# Mach3.net
KiCad netlist of a schematic drawn in Altium Designer
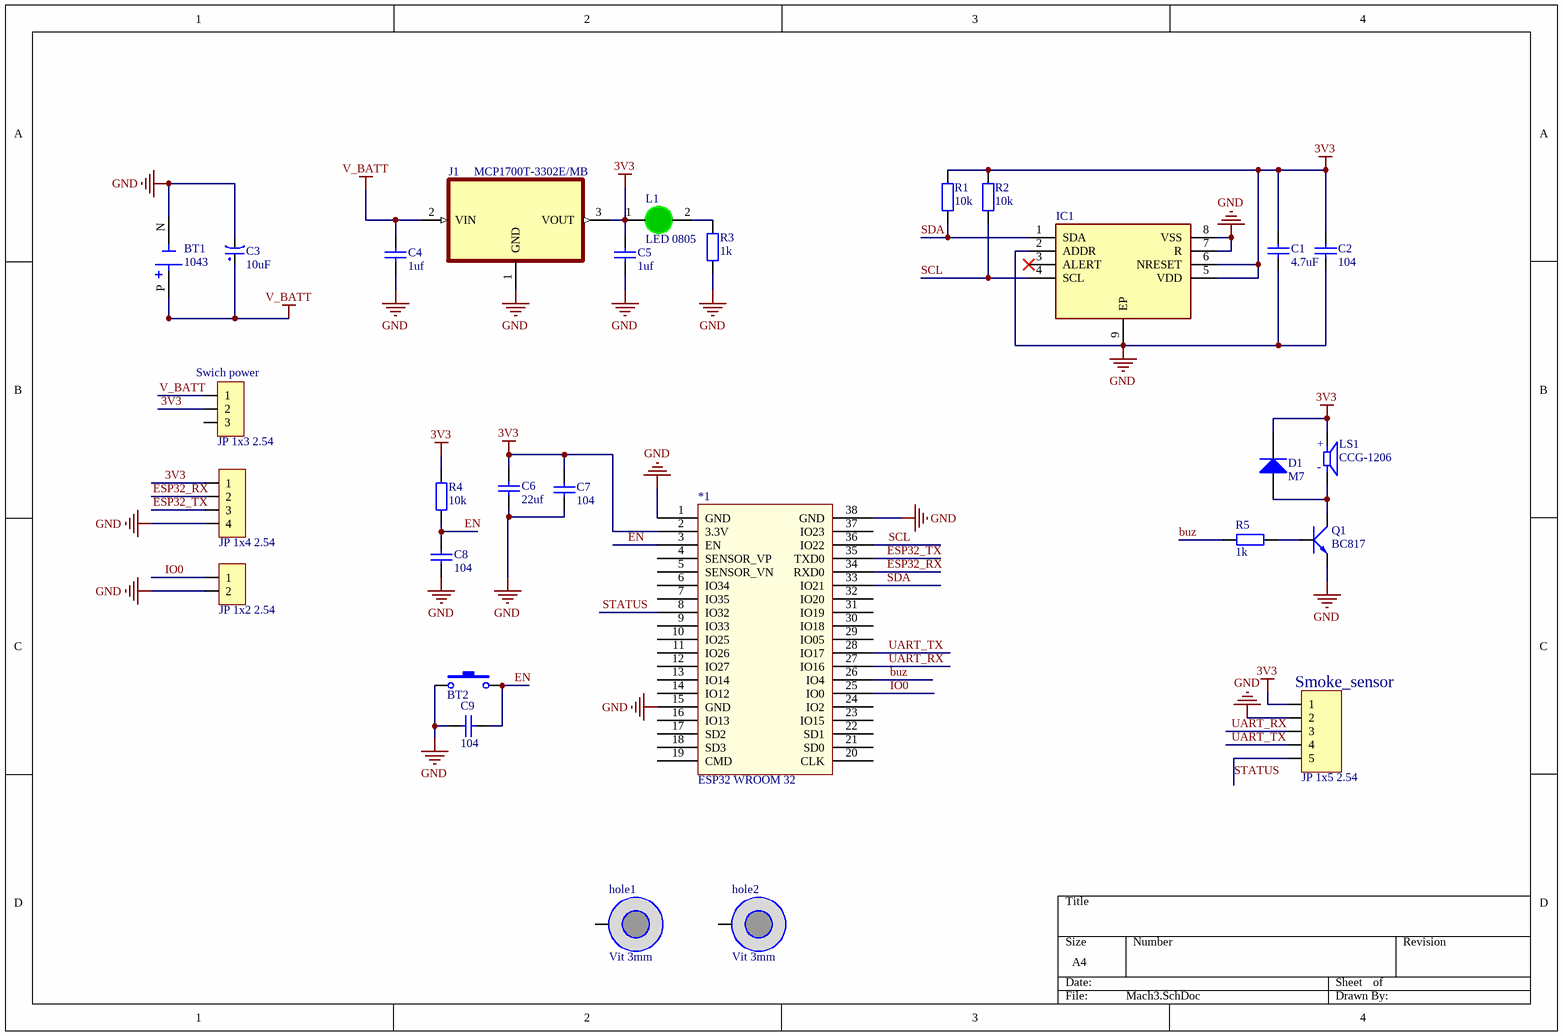
[diagram p0: Mach3.SchDoc]

(export (version "E")
  (design (tool "Eeschema 10.0.6"))
  (components
    (comp (ref "*1")
      (value "ESP32 WROOM 32")
      (footprint "ESP32-WROOM-32D")
      (libsource (lib "Altium_Lib_by_KhueNguyenCreator") (part "ESP32 WROOM 32"))
    )
    (comp (ref "BT1")
      (value "1043")
      (footprint "BAT_1043")
      (description "THM Holder for 18650 Battery")
      (fields (field (name "MF") "Keystone Electronics"))
      (libsource (lib "Mach3") (part "1043"))
    )
    (comp (ref "BT2")
      (value "Nut Nhan 2 Chan SMD 3x6x2.5")
      (footprint "Nut Nhan 2 Chan SMD 3x6x2.5")
      (libsource (lib "Altium_Lib_by_KhueNguyenCreator") (part "Nut Nhan 2 Chan SMD 3x6x2.5"))
    )
    (comp (ref "C1")
      (value "4.7uF")
      (footprint "tu 0805")
      (description "Dán")
      (libsource (lib "Altium_Lib_by_KhueNguyenCreator") (part "Tu 0805 104 50V 10%"))
    )
    (comp (ref "C2")
      (value "104")
      (footprint "tu 0805")
      (description "Dán")
      (libsource (lib "Altium_Lib_by_KhueNguyenCreator") (part "Tu 0805 104 50V 10%"))
    )
    (comp (ref "C3")
      (value "10uF")
      (footprint "tu hoa 8mm")
      (description "Cắm")
      (libsource (lib "Altium_Lib_by_KhueNguyenCreator") (part "Tu Hoa 0.1uF 50V 5x11"))
    )
    (comp (ref "C4")
      (value "1uf")
      (footprint "tu 0805")
      (description "Dán")
      (libsource (lib "Altium_Lib_by_KhueNguyenCreator") (part "Tu 0805 104 50V 10%"))
    )
    (comp (ref "C5")
      (value "1uf")
      (footprint "tu 0805")
      (description "Dán")
      (libsource (lib "Altium_Lib_by_KhueNguyenCreator") (part "Tu 0805 104 50V 10%"))
    )
    (comp (ref "C6")
      (value "22uf")
      (footprint "tu 0805")
      (description "Dán")
      (libsource (lib "Altium_Lib_by_KhueNguyenCreator") (part "Tu 0805 104 50V 10%"))
    )
    (comp (ref "C7")
      (value "104")
      (footprint "tu 0805")
      (description "Dán")
      (libsource (lib "Altium_Lib_by_KhueNguyenCreator") (part "Tu 0805 104 50V 10%"))
    )
    (comp (ref "C8")
      (value "104")
      (footprint "tu 0805")
      (description "Dán")
      (libsource (lib "Altium_Lib_by_KhueNguyenCreator") (part "Tu 0805 104 50V 10%"))
    )
    (comp (ref "C9")
      (value "104")
      (footprint "tu 0805")
      (description "Dán")
      (libsource (lib "Altium_Lib_by_KhueNguyenCreator") (part "Tu 0805 104 50V 10%"))
    )
    (comp (ref "D1")
      (value "M7")
      (footprint "DIODE SMA")
      (description "Dán")
      (libsource (lib "Altium_Lib_by_KhueNguyenCreator") (part "Diode M7 ( 4007 )"))
    )
    (comp (ref "hole1") (value "Vit 3mm") (footprint "Screw 3.0") (libsource (lib "LPSON") (part "Vit 3mm")))
    (comp (ref "hole2") (value "Vit 3mm") (footprint "Screw 3.0") (libsource (lib "LPSON") (part "Vit 3mm")))
    (comp (ref "IC1")
      (value "~")
      (footprint "SON50P250X250X100-9N-D")
      (description "Integrated Circuit")
      (fields
        (field (name "MANUFACTURER_PART_NUMBER") "SHT30-DIS-B10KS")
        (field (name "MOUSER PART NUMBER") "403-SHT30-DIS-B10KS")
      )
      (libsource (lib "Mach3") (part "SHT30-DIS-B10KS_1"))
    )
    (comp (ref "J1")
      (value "MCP1700T-3302E/MB")
      (footprint "MCP1700T-3302E/MB")
      (description "Linear Voltage Regulator IC Positive Fixed 1 Output 250mA SOT-89-3")
      (fields (field (name "MF") "Microchip"))
      (libsource (lib "Mach3") (part "MCP1700T-3302E/MB"))
    )
    (comp (ref "JP1")
      (value "JP 1x5 2.54")
      (footprint "JP 1x5 CT")
      (description "Cắm")
      (libsource (lib "Altium_Lib_by_KhueNguyenCreator") (part "JP 1x5 2.54 Cai Thang"))
    )
    (comp (ref "JP2")
      (value "JP 1x4 2.54")
      (footprint "JP 1x4 CT")
      (description "Cắm")
      (libsource (lib "Altium_Lib_by_KhueNguyenCreator") (part "JP 1x4 2.54 Cai Thang"))
    )
    (comp (ref "JP3")
      (value "JP 1x2 2.54")
      (footprint "JP 1x2 DT")
      (description "Cắm")
      (libsource (lib "Altium_Lib_by_KhueNguyenCreator") (part "JP 1x2 2.54 Duc Thang"))
    )
    (comp (ref "JP4")
      (value "JP 1x3 2.54")
      (footprint "JP 1x3 DT")
      (description "Cắm")
      (libsource (lib "Altium_Lib_by_KhueNguyenCreator") (part "JP 1x3 2.54 Duc Thang"))
    )
    (comp (ref "L1")
      (value "LED 0805")
      (footprint "LED-1206-Green")
      (description "Dán")
      (libsource (lib "Altium_Lib_by_KhueNguyenCreator") (part "LED 1206 Xanh La"))
    )
    (comp (ref "LS1")
      (value "CCG-1206")
      (footprint "CUI_CCG-1206")
      (description "12 mm, 5 V, 85 dB, Through Hole, Sealed, Magnetic Audio Transducer Buzzer")
      (fields (field (name "MF") "Same Sky"))
      (libsource (lib "Mach3") (part "CCG-1206"))
    )
    (comp (ref "Q1")
      (value "BC817")
      (footprint "SOT-23")
      (description "SOT-23 - C8658")
      (libsource (lib "Altium_Lib_by_KhueNguyenCreator") (part "Trans BC817"))
    )
    (comp (ref "R1")
      (value "10k")
      (footprint "tro smd 0805")
      (description "Dán")
      (libsource (lib "Altium_Lib_by_KhueNguyenCreator") (part "Tro 0805 1% 1k"))
    )
    (comp (ref "R2")
      (value "10k")
      (footprint "tro smd 0805")
      (description "Dán")
      (libsource (lib "Altium_Lib_by_KhueNguyenCreator") (part "Tro 0805 1% 1k"))
    )
    (comp (ref "R3")
      (value "1k")
      (footprint "tro smd 0805")
      (description "Dán")
      (libsource (lib "Altium_Lib_by_KhueNguyenCreator") (part "Tro 0805 1% 1k"))
    )
    (comp (ref "R4")
      (value "10k")
      (footprint "tro smd 0805")
      (description "Dán")
      (libsource (lib "Altium_Lib_by_KhueNguyenCreator") (part "Tro 0805 1% 1k"))
    )
    (comp (ref "R5")
      (value "1k")
      (footprint "tro smd 0805")
      (description "Dán")
      (libsource (lib "Altium_Lib_by_KhueNguyenCreator") (part "Tro 0805 1% 1k"))
    )
  )
  (nets
    (net (code "1") (name "/EN") (class "Default")
      (node (ref "*1") (pin "3") (pinfunction "EN_3") (pintype "passive"))
      (node (ref "BT2") (pin "2") (pinfunction "2_2") (pintype "passive"))
      (node (ref "C8") (pin "1") (pinfunction "1_1") (pintype "passive"))
      (node (ref "C9") (pin "2") (pinfunction "2_2") (pintype "passive"))
      (node (ref "R4") (pin "1") (pinfunction "1_1") (pintype "passive"))
    )
    (net (code "2") (name "/ESP32_RX") (class "Default")
      (node (ref "*1") (pin "34") (pinfunction "RXD0_34") (pintype "passive"))
      (node (ref "JP2") (pin "2") (pinfunction "2_2") (pintype "passive"))
    )
    (net (code "3") (name "/ESP32_TX") (class "Default")
      (node (ref "*1") (pin "35") (pinfunction "TXD0_35") (pintype "passive"))
      (node (ref "JP2") (pin "3") (pinfunction "3_3") (pintype "passive"))
    )
    (net (code "4") (name "/IO0") (class "Default")
      (node (ref "*1") (pin "25") (pinfunction "IO0_25") (pintype "passive"))
      (node (ref "JP3") (pin "1") (pinfunction "1_1") (pintype "passive"))
    )
    (net (code "5") (name "/SCL") (class "Default")
      (node (ref "*1") (pin "36") (pinfunction "IO22_36") (pintype "passive"))
      (node (ref "IC1") (pin "4") (pinfunction "SCL_4") (pintype "passive"))
      (node (ref "R2") (pin "1") (pinfunction "1_1") (pintype "passive"))
    )
    (net (code "6") (name "/SDA") (class "Default")
      (node (ref "*1") (pin "33") (pinfunction "IO21_33") (pintype "passive"))
      (node (ref "IC1") (pin "1") (pinfunction "SDA_1") (pintype "passive"))
      (node (ref "R1") (pin "1") (pinfunction "1_1") (pintype "passive"))
    )
    (net (code "7") (name "/STATUS") (class "Default")
      (node (ref "*1") (pin "8") (pinfunction "IO32_8") (pintype "passive"))
      (node (ref "JP1") (pin "5") (pinfunction "5_5") (pintype "passive"))
    )
    (net (code "8") (name "/UART_RX") (class "Default")
      (node (ref "*1") (pin "27") (pinfunction "IO16_27") (pintype "passive"))
      (node (ref "JP1") (pin "3") (pinfunction "3_3") (pintype "passive"))
    )
    (net (code "9") (name "/UART_TX") (class "Default")
      (node (ref "*1") (pin "28") (pinfunction "IO17_28") (pintype "passive"))
      (node (ref "JP1") (pin "4") (pinfunction "4_4") (pintype "passive"))
    )
    (net (code "10") (name "/buz") (class "Default")
      (node (ref "*1") (pin "26") (pinfunction "IO4_26") (pintype "passive"))
      (node (ref "R5") (pin "2") (pinfunction "2_2") (pintype "passive"))
    )
    (net (code "11") (name "3V3") (class "Default")
      (node (ref "*1") (pin "2") (pinfunction "3.3V_2") (pintype "passive"))
      (node (ref "C1") (pin "1") (pinfunction "1_1") (pintype "passive"))
      (node (ref "C2") (pin "1") (pinfunction "1_1") (pintype "passive"))
      (node (ref "C5") (pin "1") (pinfunction "1_1") (pintype "passive"))
      (node (ref "C6") (pin "1") (pinfunction "1_1") (pintype "passive"))
      (node (ref "C7") (pin "1") (pinfunction "1_1") (pintype "passive"))
      (node (ref "D1") (pin "2") (pinfunction "K_2") (pintype "passive"))
      (node (ref "IC1") (pin "5") (pinfunction "VDD_5") (pintype "passive"))
      (node (ref "IC1") (pin "6") (pinfunction "NRESET_6") (pintype "passive"))
      (node (ref "J1") (pin "3") (pinfunction "VOUT_3") (pintype "output"))
      (node (ref "JP1") (pin "1") (pinfunction "1_1") (pintype "passive"))
      (node (ref "JP2") (pin "1") (pinfunction "1_1") (pintype "passive"))
      (node (ref "JP4") (pin "2") (pinfunction "2_2") (pintype "passive"))
      (node (ref "L1") (pin "1") (pinfunction "A_1") (pintype "passive"))
      (node (ref "LS1") (pin "P") (pinfunction "P_P") (pintype "passive"))
      (node (ref "R1") (pin "2") (pinfunction "2_2") (pintype "passive"))
      (node (ref "R2") (pin "2") (pinfunction "2_2") (pintype "passive"))
      (node (ref "R4") (pin "2") (pinfunction "2_2") (pintype "passive"))
    )
    (net (code "12") (name "GND") (class "Default")
      (node (ref "*1") (pin "1") (pinfunction "GND_1") (pintype "passive"))
      (node (ref "*1") (pin "15") (pinfunction "GND_15") (pintype "passive"))
      (node (ref "*1") (pin "38") (pinfunction "GND_38") (pintype "passive"))
      (node (ref "BT1") (pin "N") (pinfunction "NEG_N") (pintype "passive"))
      (node (ref "BT2") (pin "1") (pinfunction "1_1") (pintype "passive"))
      (node (ref "C1") (pin "2") (pinfunction "2_2") (pintype "passive"))
      (node (ref "C2") (pin "2") (pinfunction "2_2") (pintype "passive"))
      (node (ref "C3") (pin "2") (pinfunction "2_2") (pintype "passive"))
      (node (ref "C4") (pin "2") (pinfunction "2_2") (pintype "passive"))
      (node (ref "C5") (pin "2") (pinfunction "2_2") (pintype "passive"))
      (node (ref "C6") (pin "2") (pinfunction "2_2") (pintype "passive"))
      (node (ref "C7") (pin "2") (pinfunction "2_2") (pintype "passive"))
      (node (ref "C8") (pin "2") (pinfunction "2_2") (pintype "passive"))
      (node (ref "C9") (pin "1") (pinfunction "1_1") (pintype "passive"))
      (node (ref "IC1") (pin "2") (pinfunction "ADDR_2") (pintype "passive"))
      (node (ref "IC1") (pin "7") (pinfunction "R_7") (pintype "passive"))
      (node (ref "IC1") (pin "8") (pinfunction "VSS_8") (pintype "passive"))
      (node (ref "IC1") (pin "9") (pinfunction "EP_9") (pintype "passive"))
      (node (ref "J1") (pin "1") (pinfunction "GND_1") (pintype "passive"))
      (node (ref "JP1") (pin "2") (pinfunction "2_2") (pintype "passive"))
      (node (ref "JP2") (pin "4") (pinfunction "4_4") (pintype "passive"))
      (node (ref "JP3") (pin "2") (pinfunction "2_2") (pintype "passive"))
      (node (ref "Q1") (pin "2") (pinfunction "E_2") (pintype "passive"))
      (node (ref "R3") (pin "1") (pinfunction "1_1") (pintype "passive"))
    )
    (net (code "13") (name "Net-(D1-A)") (class "Default")
      (node (ref "D1") (pin "1") (pinfunction "A_1") (pintype "passive"))
      (node (ref "LS1") (pin "M") (pinfunction "M_M") (pintype "passive"))
      (node (ref "Q1") (pin "3") (pinfunction "C_3") (pintype "passive"))
    )
    (net (code "14") (name "Net-(L1-K)") (class "Default")
      (node (ref "L1") (pin "2") (pinfunction "K_2") (pintype "passive"))
      (node (ref "R3") (pin "2") (pinfunction "2_2") (pintype "passive"))
    )
    (net (code "15") (name "Net-(Q1-B)") (class "Default")
      (node (ref "Q1") (pin "1") (pinfunction "B_1") (pintype "passive"))
      (node (ref "R5") (pin "1") (pinfunction "1_1") (pintype "passive"))
    )
    (net (code "16") (name "V_BATT") (class "Default")
      (node (ref "BT1") (pin "P") (pinfunction "POS_P") (pintype "passive"))
      (node (ref "C3") (pin "1") (pinfunction "1_1") (pintype "passive"))
      (node (ref "C4") (pin "1") (pinfunction "1_1") (pintype "passive"))
      (node (ref "J1") (pin "2") (pinfunction "VIN_2") (pintype "input"))
      (node (ref "JP4") (pin "1") (pinfunction "1_1") (pintype "passive"))
    )
    (net (code "17") (name "unconnected-(*1-CLK-Pad20)") (class "Default")
      (node (ref "*1") (pin "20") (pinfunction "CLK_20") (pintype "passive"))
    )
    (net (code "18") (name "unconnected-(*1-CMD-Pad19)") (class "Default")
      (node (ref "*1") (pin "19") (pinfunction "CMD_19") (pintype "passive"))
    )
    (net (code "19") (name "unconnected-(*1-IO2-Pad24)") (class "Default")
      (node (ref "*1") (pin "24") (pinfunction "IO2_24") (pintype "passive"))
    )
    (net (code "20") (name "unconnected-(*1-IO05-Pad29)") (class "Default")
      (node (ref "*1") (pin "29") (pinfunction "IO05_29") (pintype "passive"))
    )
    (net (code "21") (name "unconnected-(*1-IO12-Pad14)") (class "Default")
      (node (ref "*1") (pin "14") (pinfunction "IO12_14") (pintype "passive"))
    )
    (net (code "22") (name "unconnected-(*1-IO13-Pad16)") (class "Default")
      (node (ref "*1") (pin "16") (pinfunction "IO13_16") (pintype "passive"))
    )
    (net (code "23") (name "unconnected-(*1-IO14-Pad13)") (class "Default")
      (node (ref "*1") (pin "13") (pinfunction "IO14_13") (pintype "passive"))
    )
    (net (code "24") (name "unconnected-(*1-IO15-Pad23)") (class "Default")
      (node (ref "*1") (pin "23") (pinfunction "IO15_23") (pintype "passive"))
    )
    (net (code "25") (name "unconnected-(*1-IO18-Pad30)") (class "Default")
      (node (ref "*1") (pin "30") (pinfunction "IO18_30") (pintype "passive"))
    )
    (net (code "26") (name "unconnected-(*1-IO19-Pad31)") (class "Default")
      (node (ref "*1") (pin "31") (pinfunction "IO19_31") (pintype "passive"))
    )
    (net (code "27") (name "unconnected-(*1-IO20-Pad32)") (class "Default")
      (node (ref "*1") (pin "32") (pinfunction "IO20_32") (pintype "passive"))
    )
    (net (code "28") (name "unconnected-(*1-IO23-Pad37)") (class "Default")
      (node (ref "*1") (pin "37") (pinfunction "IO23_37") (pintype "passive"))
    )
    (net (code "29") (name "unconnected-(*1-IO25-Pad10)") (class "Default")
      (node (ref "*1") (pin "10") (pinfunction "IO25_10") (pintype "passive"))
    )
    (net (code "30") (name "unconnected-(*1-IO26-Pad11)") (class "Default")
      (node (ref "*1") (pin "11") (pinfunction "IO26_11") (pintype "passive"))
    )
    (net (code "31") (name "unconnected-(*1-IO27-Pad12)") (class "Default")
      (node (ref "*1") (pin "12") (pinfunction "IO27_12") (pintype "passive"))
    )
    (net (code "32") (name "unconnected-(*1-IO33-Pad9)") (class "Default")
      (node (ref "*1") (pin "9") (pinfunction "IO33_9") (pintype "passive"))
    )
    (net (code "33") (name "unconnected-(*1-IO34-Pad6)") (class "Default")
      (node (ref "*1") (pin "6") (pinfunction "IO34_6") (pintype "passive"))
    )
    (net (code "34") (name "unconnected-(*1-IO35-Pad7)") (class "Default")
      (node (ref "*1") (pin "7") (pinfunction "IO35_7") (pintype "passive"))
    )
    (net (code "35") (name "unconnected-(*1-SD0-Pad21)") (class "Default")
      (node (ref "*1") (pin "21") (pinfunction "SD0_21") (pintype "passive"))
    )
    (net (code "36") (name "unconnected-(*1-SD1-Pad22)") (class "Default")
      (node (ref "*1") (pin "22") (pinfunction "SD1_22") (pintype "passive"))
    )
    (net (code "37") (name "unconnected-(*1-SD2-Pad17)") (class "Default")
      (node (ref "*1") (pin "17") (pinfunction "SD2_17") (pintype "passive"))
    )
    (net (code "38") (name "unconnected-(*1-SD3-Pad18)") (class "Default")
      (node (ref "*1") (pin "18") (pinfunction "SD3_18") (pintype "passive"))
    )
    (net (code "39") (name "unconnected-(*1-SENSOR_VN-Pad5)") (class "Default")
      (node (ref "*1") (pin "5") (pinfunction "SENSOR_VN_5") (pintype "passive"))
    )
    (net (code "40") (name "unconnected-(*1-SENSOR_VP-Pad4)") (class "Default")
      (node (ref "*1") (pin "4") (pinfunction "SENSOR_VP_4") (pintype "passive"))
    )
    (net (code "41") (name "unconnected-(IC1-ALERT-Pad3)") (class "Default")
      (node (ref "IC1") (pin "3") (pinfunction "ALERT_3") (pintype "passive+no_connect"))
    )
    (net (code "42") (name "unconnected-(JP4-Pad3)") (class "Default")
      (node (ref "JP4") (pin "3") (pinfunction "3_3") (pintype "passive"))
    )
    (net (code "43") (name "unconnected-(hole1-hole-Pad1)") (class "Default")
      (node (ref "hole1") (pin "1") (pinfunction "hole_1") (pintype "passive"))
    )
    (net (code "44") (name "unconnected-(hole2-hole-Pad1)") (class "Default")
      (node (ref "hole2") (pin "1") (pinfunction "hole_1") (pintype "passive"))
    )
  )
)
